# CurrentSensorV2_0.net
KiCad netlist of a schematic drawn in EAGLE
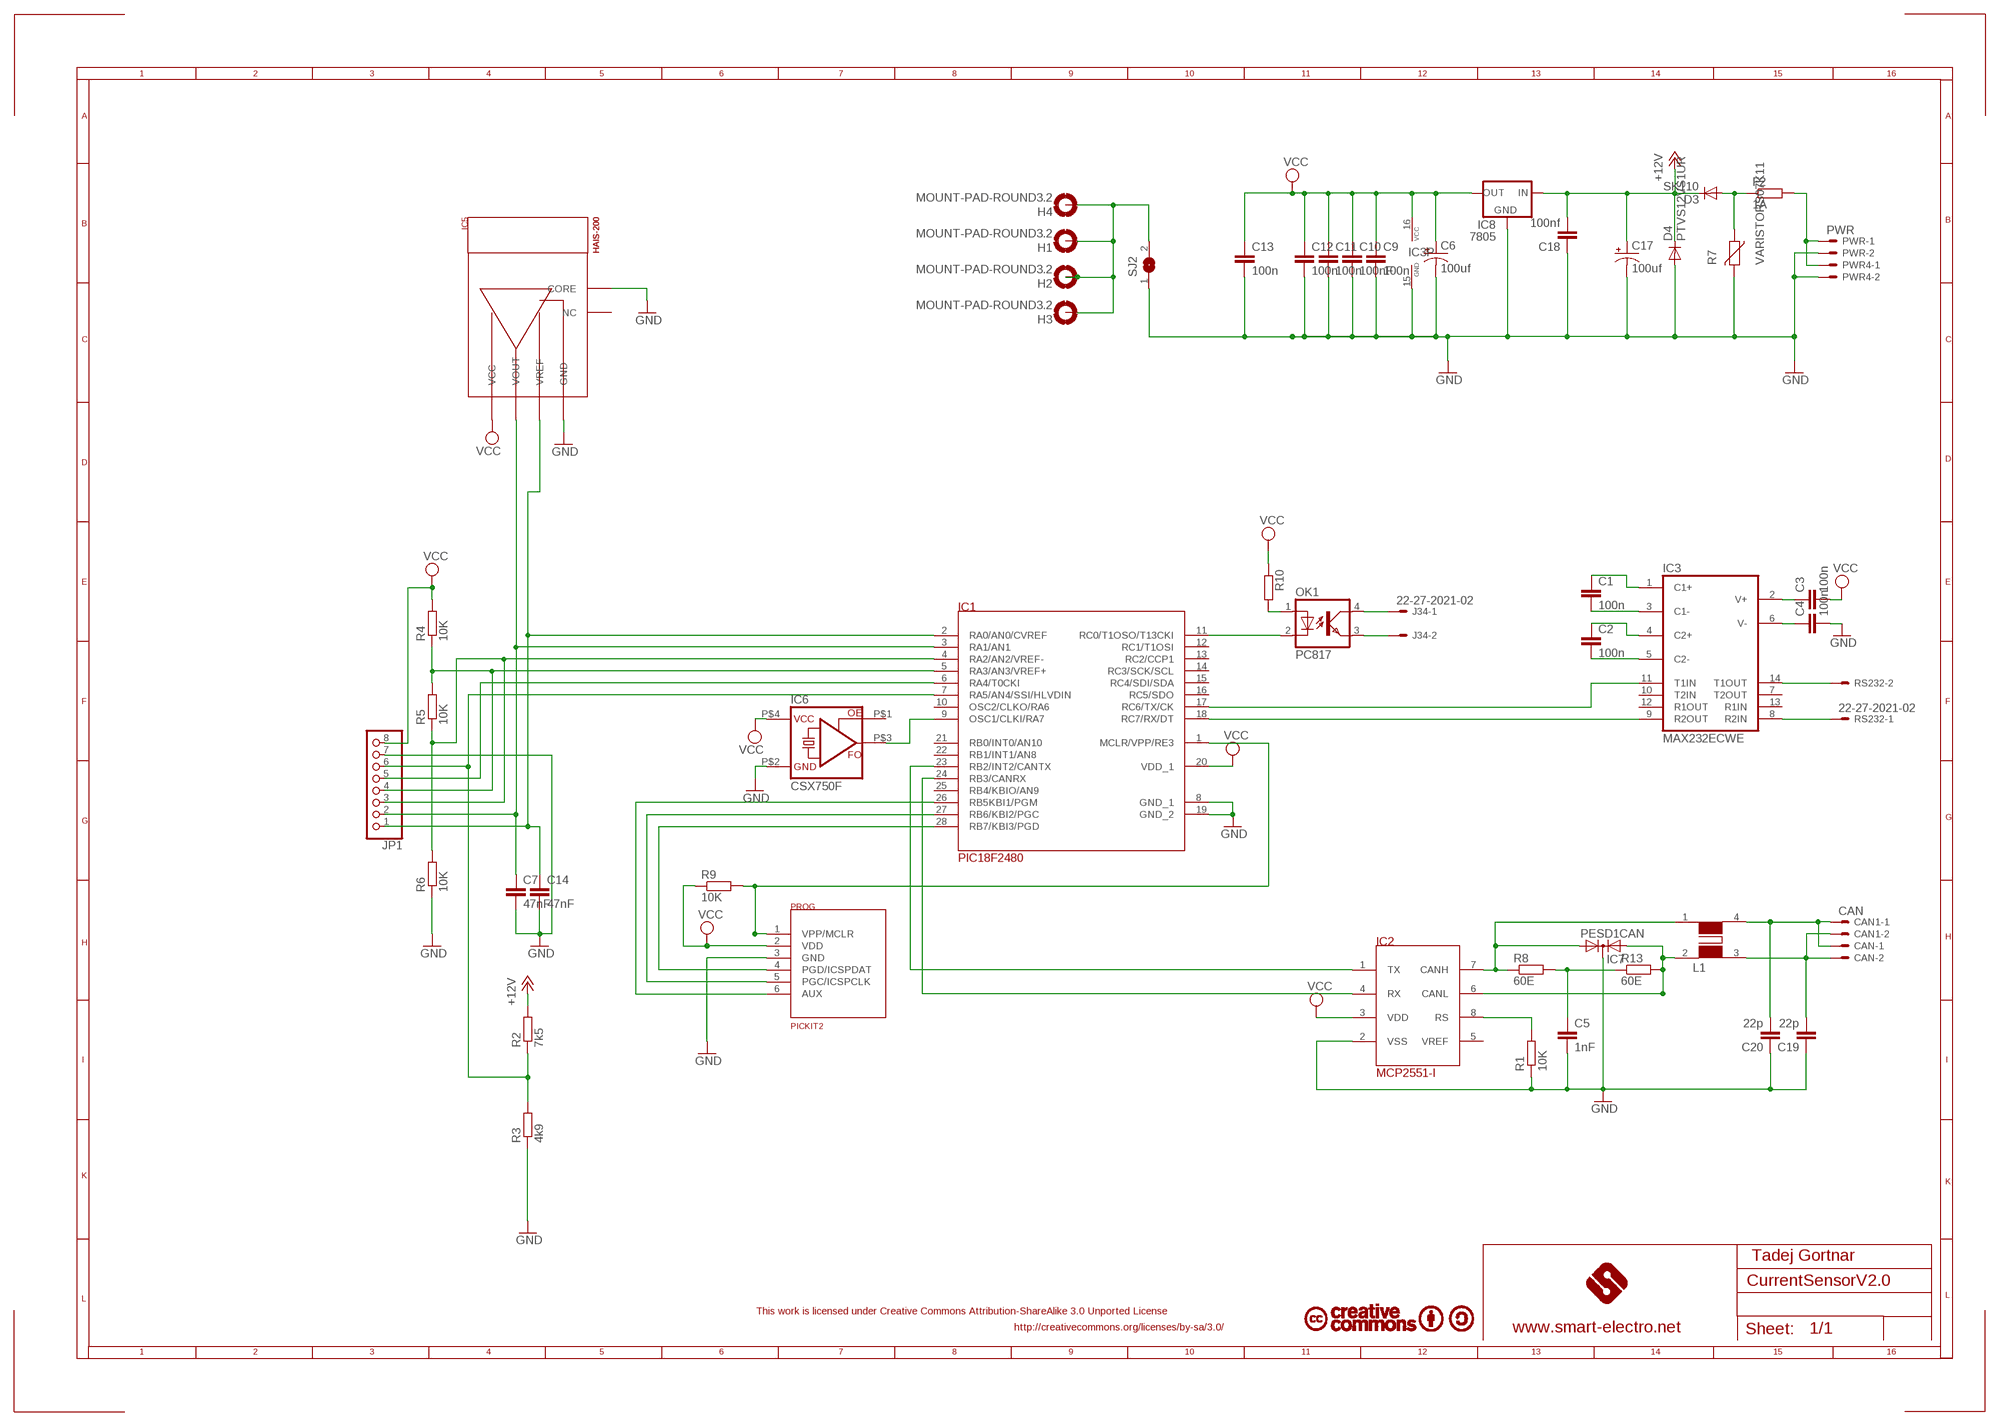
[diagram p0: schematic, sheet 1]

(export (version "E")
  (design (tool "Eeschema 10.0.6"))
  (components
    (comp (ref "C1")
      (value "100n")
      (footprint "eagle-import:C0805K")
      (libsource (lib "eagle-import") (part "C-EUC0805K"))
    )
    (comp (ref "C2")
      (value "100n")
      (footprint "eagle-import:C0805K")
      (libsource (lib "eagle-import") (part "C-EUC0805K"))
    )
    (comp (ref "C3")
      (value "100n")
      (footprint "eagle-import:C0805K")
      (libsource (lib "eagle-import") (part "C-EUC0805K"))
    )
    (comp (ref "C4")
      (value "100n")
      (footprint "eagle-import:C0805K")
      (libsource (lib "eagle-import") (part "C-EUC0805K"))
    )
    (comp (ref "C5")
      (value "1nF")
      (footprint "eagle-import:C0805")
      (libsource (lib "eagle-import") (part "C-EUC0805"))
    )
    (comp (ref "C6")
      (value "100uf")
      (footprint "eagle-import:PANASONIC_C")
      (libsource (lib "eagle-import") (part "CPOL-USC"))
    )
    (comp (ref "C7")
      (value "47nF")
      (footprint "eagle-import:C0805K")
      (libsource (lib "eagle-import") (part "C-EUC0805K"))
    )
    (comp (ref "C9")
      (value "100n")
      (footprint "eagle-import:C0805K")
      (libsource (lib "eagle-import") (part "C-EUC0805K"))
    )
    (comp (ref "C10")
      (value "100nF")
      (footprint "eagle-import:C0805K")
      (libsource (lib "eagle-import") (part "C-EUC0805K"))
    )
    (comp (ref "C11")
      (value "100n")
      (footprint "eagle-import:C0805K")
      (libsource (lib "eagle-import") (part "C-EUC0805K"))
    )
    (comp (ref "C12")
      (value "100n")
      (footprint "eagle-import:C0805K")
      (libsource (lib "eagle-import") (part "C-EUC0805K"))
    )
    (comp (ref "C13")
      (value "100n")
      (footprint "eagle-import:C0805K")
      (libsource (lib "eagle-import") (part "C-EUC0805K"))
    )
    (comp (ref "C14")
      (value "47nF")
      (footprint "eagle-import:C0805K")
      (libsource (lib "eagle-import") (part "C-EUC0805K"))
    )
    (comp (ref "C17")
      (value "100uf")
      (footprint "eagle-import:PANASONIC_C")
      (libsource (lib "eagle-import") (part "CPOL-USC"))
    )
    (comp (ref "C18")
      (value "100nf")
      (footprint "eagle-import:C0805")
      (libsource (lib "eagle-import") (part "resistor_C-EUC0805"))
    )
    (comp (ref "C19")
      (value "22p")
      (footprint "eagle-import:C0805")
      (libsource (lib "eagle-import") (part "C-EUC0805"))
    )
    (comp (ref "C20")
      (value "22p")
      (footprint "eagle-import:C0805")
      (libsource (lib "eagle-import") (part "C-EUC0805"))
    )
    (comp (ref "CAN")
      (value "CAN")
      (footprint "eagle-import:6410-02")
      (libsource (lib "eagle-import") (part "22-?-0227-2021"))
    )
    (comp (ref "CAN1")
      (value "CAN")
      (footprint "eagle-import:6410-02")
      (libsource (lib "eagle-import") (part "22-?-0227-2021"))
    )
    (comp (ref "D3")
      (value "SK110")
      (footprint "eagle-import:MINIMELF")
      (libsource (lib "eagle-import") (part "DIODE-MINIMELF"))
    )
    (comp (ref "D4")
      (value "PTVS12VS1UR")
      (footprint "eagle-import:SOD323-W")
      (libsource (lib "eagle-import") (part "DIODE-SOD323-W"))
    )
    (comp (ref "F2")
      (value "1A")
      (footprint "eagle-import:R1206")
      (libsource (lib "eagle-import") (part "resistor_R-EU_R1206"))
    )
    (comp (ref "H1")
      (value "MOUNT-PAD-ROUND3.2")
      (footprint "eagle-import:3,2-PAD")
      (libsource (lib "eagle-import") (part "MOUNT-PAD-ROUND3.2"))
    )
    (comp (ref "H2")
      (value "MOUNT-PAD-ROUND3.2")
      (footprint "eagle-import:3,2-PAD")
      (libsource (lib "eagle-import") (part "MOUNT-PAD-ROUND3.2"))
    )
    (comp (ref "H3")
      (value "MOUNT-PAD-ROUND3.2")
      (footprint "eagle-import:3,2-PAD")
      (libsource (lib "eagle-import") (part "MOUNT-PAD-ROUND3.2"))
    )
    (comp (ref "H4")
      (value "MOUNT-PAD-ROUND3.2")
      (footprint "eagle-import:3,2-PAD")
      (libsource (lib "eagle-import") (part "MOUNT-PAD-ROUND3.2"))
    )
    (comp (ref "IC1")
      (value "PIC18F2480")
      (footprint "eagle-import:SO-28W")
      (libsource (lib "eagle-import") (part "PIC18F280"))
    )
    (comp (ref "IC2")
      (value "MCP2551-I")
      (footprint "eagle-import:SO-08")
      (libsource (lib "eagle-import") (part "MCP2551"))
    )
    (comp (ref "IC3")
      (value "MAX232ECWE")
      (footprint "eagle-import:SO16L")
      (libsource (lib "eagle-import") (part "MAX232ECWE"))
    )
    (comp (ref "IC5")
      (value "HAIS-200")
      (footprint "eagle-import:HAIS-P")
      (libsource (lib "eagle-import") (part "HAIS-200"))
    )
    (comp (ref "IC6")
      (value "CSX750F")
      (footprint "eagle-import:CSX750")
      (libsource (lib "eagle-import") (part "CSX750F"))
    )
    (comp (ref "IC7")
      (value "PESD1CAN")
      (footprint "eagle-import:SOT23")
      (libsource (lib "eagle-import") (part "BAS70-06"))
    )
    (comp (ref "IC8")
      (value "7805")
      (footprint "eagle-import:SOT223")
      (libsource (lib "eagle-import") (part "78XXS'SOT223'"))
    )
    (comp (ref "J34")
      (value "22-27-2021-02")
      (footprint "eagle-import:6410-02")
      (libsource (lib "eagle-import") (part "22-?-0227-2021"))
    )
    (comp (ref "JP1")
      (value "PINHD-1X8")
      (footprint "eagle-import:1X08")
      (libsource (lib "eagle-import") (part "PINHD-1X8"))
    )
    (comp (ref "L1")
      (value "WE-DD_M/S")
      (footprint "eagle-import:WE-DD_M_S")
      (libsource (lib "eagle-import") (part "WE-DD_M/S"))
    )
    (comp (ref "OK1")
      (value "PC817")
      (footprint "eagle-import:DIL04")
      (libsource (lib "eagle-import") (part "PC817"))
    )
    (comp (ref "PROG")
      (value "PICKIT2")
      (footprint "eagle-import:PINHD-1X6")
      (libsource (lib "eagle-import") (part "PICKIT2"))
    )
    (comp (ref "PWR")
      (value "PWR")
      (footprint "eagle-import:6410-02")
      (libsource (lib "eagle-import") (part "22-?-0227-2021"))
    )
    (comp (ref "PWR4")
      (value "PWR")
      (footprint "eagle-import:6410-02")
      (libsource (lib "eagle-import") (part "22-?-0227-2021"))
    )
    (comp (ref "R1")
      (value "10K")
      (footprint "eagle-import:M0805")
      (libsource (lib "eagle-import") (part "R-EU_M0805"))
    )
    (comp (ref "R2")
      (value "7k5")
      (footprint "eagle-import:M0805")
      (libsource (lib "eagle-import") (part "R-EU_M0805"))
    )
    (comp (ref "R3")
      (value "4k9")
      (footprint "eagle-import:M0805")
      (libsource (lib "eagle-import") (part "R-EU_M0805"))
    )
    (comp (ref "R4")
      (value "10K")
      (footprint "eagle-import:M0805")
      (libsource (lib "eagle-import") (part "R-EU_M0805"))
    )
    (comp (ref "R5")
      (value "10K")
      (footprint "eagle-import:M0805")
      (libsource (lib "eagle-import") (part "R-EU_M0805"))
    )
    (comp (ref "R6")
      (value "10K")
      (footprint "eagle-import:M0805")
      (libsource (lib "eagle-import") (part "R-EU_M0805"))
    )
    (comp (ref "R7")
      (value "VARISTORS07K11")
      (footprint "eagle-import:S07K11")
      (libsource (lib "eagle-import") (part "VARISTORS07K11"))
    )
    (comp (ref "R8")
      (value "60E")
      (footprint "eagle-import:R0805")
      (libsource (lib "eagle-import") (part "R-EU_R0805"))
    )
    (comp (ref "R9")
      (value "10K")
      (footprint "eagle-import:M0805")
      (libsource (lib "eagle-import") (part "R-EU_M0805"))
    )
    (comp (ref "R10")
      (value "R-EU_M0805")
      (footprint "eagle-import:M0805")
      (libsource (lib "eagle-import") (part "R-EU_M0805"))
    )
    (comp (ref "R13")
      (value "60E")
      (footprint "eagle-import:R0805")
      (libsource (lib "eagle-import") (part "R-EU_R0805"))
    )
    (comp (ref "RS232")
      (value "22-27-2021-02")
      (footprint "eagle-import:6410-02")
      (libsource (lib "eagle-import") (part "22-?-0227-2021"))
    )
    (comp (ref "SJ2") (value "SJ") (footprint "eagle-import:SJ") (libsource (lib "eagle-import") (part "SJ")))
  )
  (nets
    (net (code "1") (name "+12V") (class "Default")
      (node (ref "C17") (pin "+") (pinfunction "+_+") (pintype "passive"))
      (node (ref "C18") (pin "2") (pinfunction "2_2") (pintype "passive"))
      (node (ref "D3") (pin "C") (pinfunction "C_C") (pintype "passive"))
      (node (ref "D4") (pin "C") (pinfunction "C_C") (pintype "passive"))
      (node (ref "IC8") (pin "1") (pinfunction "IN_1") (pintype "input"))
      (node (ref "R2") (pin "2") (pinfunction "2_2") (pintype "passive"))
    )
    (net (code "2") (name "GND") (class "Default")
      (node (ref "C10") (pin "2") (pinfunction "2_2") (pintype "passive"))
      (node (ref "C11") (pin "2") (pinfunction "2_2") (pintype "passive"))
      (node (ref "C12") (pin "2") (pinfunction "2_2") (pintype "passive"))
      (node (ref "C13") (pin "2") (pinfunction "2_2") (pintype "passive"))
      (node (ref "C14") (pin "2") (pinfunction "2_2") (pintype "passive"))
      (node (ref "C17") (pin "-") (pinfunction "-_-") (pintype "passive"))
      (node (ref "C18") (pin "1") (pinfunction "1_1") (pintype "passive"))
      (node (ref "C19") (pin "1") (pinfunction "1_1") (pintype "passive"))
      (node (ref "C20") (pin "1") (pinfunction "1_1") (pintype "passive"))
      (node (ref "C4") (pin "2") (pinfunction "2_2") (pintype "passive"))
      (node (ref "C5") (pin "2") (pinfunction "2_2") (pintype "passive"))
      (node (ref "C6") (pin "-") (pinfunction "-_-") (pintype "passive"))
      (node (ref "C7") (pin "2") (pinfunction "2_2") (pintype "passive"))
      (node (ref "C9") (pin "2") (pinfunction "2_2") (pintype "passive"))
      (node (ref "D4") (pin "A") (pinfunction "A_A") (pintype "passive"))
      (node (ref "IC1") (pin "19") (pinfunction "GND_2_19") (pintype "power_in"))
      (node (ref "IC1") (pin "8") (pinfunction "GND_1_8") (pintype "power_in"))
      (node (ref "IC2") (pin "2") (pinfunction "VSS_2") (pintype "power_in"))
      (node (ref "IC3") (pin "15") (pinfunction "GND_15") (pintype "power_in"))
      (node (ref "IC5") (pin "P$2") (pinfunction "GND_P$2") (pintype "power_in"))
      (node (ref "IC5") (pin "P$5") (pinfunction "CORE_P$5") (pintype "passive"))
      (node (ref "IC6") (pin "P$2") (pinfunction "GND_P$2") (pintype "power_in"))
      (node (ref "IC7") (pin "3") (pinfunction "C_3") (pintype "passive"))
      (node (ref "IC8") (pin "2") (pinfunction "GND_2") (pintype "input"))
      (node (ref "JP1") (pin "7") (pinfunction "7_7") (pintype "passive"))
      (node (ref "PROG") (pin "3") (pinfunction "GND_3") (pintype "bidirectional"))
      (node (ref "PWR") (pin "2") (pinfunction "S_2") (pintype "passive"))
      (node (ref "PWR4") (pin "2") (pinfunction "S_2") (pintype "passive"))
      (node (ref "R1") (pin "1") (pinfunction "1_1") (pintype "passive"))
      (node (ref "R3") (pin "1") (pinfunction "1_1") (pintype "passive"))
      (node (ref "R6") (pin "1") (pinfunction "1_1") (pintype "passive"))
      (node (ref "R7") (pin "2") (pinfunction "2_2") (pintype "passive"))
      (node (ref "SJ2") (pin "1") (pinfunction "1_1") (pintype "passive"))
    )
    (net (code "3") (name "Net-(C5-Pad1)") (class "Default")
      (node (ref "C5") (pin "1") (pinfunction "1_1") (pintype "passive"))
      (node (ref "R13") (pin "1") (pinfunction "1_1") (pintype "passive"))
      (node (ref "R8") (pin "2") (pinfunction "2_2") (pintype "passive"))
    )
    (net (code "4") (name "Net-(CAN1A-S)") (class "Default")
      (node (ref "C20") (pin "2") (pinfunction "2_2") (pintype "passive"))
      (node (ref "CAN") (pin "1") (pinfunction "S_1") (pintype "passive"))
      (node (ref "CAN1") (pin "1") (pinfunction "S_1") (pintype "passive"))
      (node (ref "L1") (pin "4") (pinfunction "3_4") (pintype "passive"))
    )
    (net (code "5") (name "Net-(CAN1B-S)") (class "Default")
      (node (ref "C19") (pin "2") (pinfunction "2_2") (pintype "passive"))
      (node (ref "CAN") (pin "2") (pinfunction "S_2") (pintype "passive"))
      (node (ref "CAN1") (pin "2") (pinfunction "S_2") (pintype "passive"))
      (node (ref "L1") (pin "3") (pinfunction "4_3") (pintype "passive"))
    )
    (net (code "6") (name "Net-(D3-PadA)") (class "Default")
      (node (ref "D3") (pin "A") (pinfunction "A_A") (pintype "passive"))
      (node (ref "F2") (pin "1") (pinfunction "1_1") (pintype "passive"))
      (node (ref "R7") (pin "1") (pinfunction "1_1") (pintype "passive"))
    )
    (net (code "7") (name "Net-(H1-MOUNT)") (class "Default")
      (node (ref "H1") (pin "B3,2") (pinfunction "MOUNT_B3,2") (pintype "passive"))
      (node (ref "H2") (pin "B3,2") (pinfunction "MOUNT_B3,2") (pintype "passive"))
      (node (ref "H3") (pin "B3,2") (pinfunction "MOUNT_B3,2") (pintype "passive"))
      (node (ref "H4") (pin "B3,2") (pinfunction "MOUNT_B3,2") (pintype "passive"))
      (node (ref "SJ2") (pin "2") (pinfunction "2_2") (pintype "passive"))
    )
    (net (code "8") (name "Net-(IC1-MCLR{slash}VPP{slash}RE3)") (class "Default")
      (node (ref "IC1") (pin "1") (pinfunction "MCLR/VPP/RE3_1") (pintype "input"))
      (node (ref "PROG") (pin "1") (pinfunction "VPP/MCLR_1") (pintype "bidirectional"))
      (node (ref "R9") (pin "2") (pinfunction "2_2") (pintype "passive"))
    )
    (net (code "9") (name "Net-(IC1-OSC1{slash}CLKI{slash}RA7)") (class "Default")
      (node (ref "IC1") (pin "9") (pinfunction "OSC1/CLKI/RA7_9") (pintype "bidirectional"))
      (node (ref "IC6") (pin "P$3") (pinfunction "FO_P$3") (pintype "output"))
    )
    (net (code "10") (name "Net-(IC1-RA0{slash}AN0{slash}CVREF)") (class "Default")
      (node (ref "C14") (pin "1") (pinfunction "1_1") (pintype "passive"))
      (node (ref "IC1") (pin "2") (pinfunction "RA0/AN0/CVREF_2") (pintype "bidirectional"))
      (node (ref "IC5") (pin "P$4") (pinfunction "VREF_P$4") (pintype "output"))
      (node (ref "JP1") (pin "1") (pinfunction "1_1") (pintype "passive"))
    )
    (net (code "11") (name "Net-(IC1-RA1{slash}AN1)") (class "Default")
      (node (ref "C7") (pin "1") (pinfunction "1_1") (pintype "passive"))
      (node (ref "IC1") (pin "3") (pinfunction "RA1/AN1_3") (pintype "bidirectional"))
      (node (ref "IC5") (pin "P$3") (pinfunction "VOUT_P$3") (pintype "output"))
      (node (ref "JP1") (pin "2") (pinfunction "2_2") (pintype "passive"))
    )
    (net (code "12") (name "Net-(IC1-RA2{slash}AN2{slash}VREF-)") (class "Default")
      (node (ref "IC1") (pin "4") (pinfunction "RA2/AN2/VREF-_4") (pintype "bidirectional"))
      (node (ref "JP1") (pin "3") (pinfunction "3_3") (pintype "passive"))
      (node (ref "R5") (pin "1") (pinfunction "1_1") (pintype "passive"))
      (node (ref "R6") (pin "2") (pinfunction "2_2") (pintype "passive"))
    )
    (net (code "13") (name "Net-(IC1-RA3{slash}AN3{slash}VREF+)") (class "Default")
      (node (ref "IC1") (pin "5") (pinfunction "RA3/AN3/VREF+_5") (pintype "bidirectional"))
      (node (ref "JP1") (pin "4") (pinfunction "4_4") (pintype "passive"))
      (node (ref "R4") (pin "1") (pinfunction "1_1") (pintype "passive"))
      (node (ref "R5") (pin "2") (pinfunction "2_2") (pintype "passive"))
    )
    (net (code "14") (name "Net-(IC1-RA4{slash}T0CKI)") (class "Default")
      (node (ref "IC1") (pin "6") (pinfunction "RA4/T0CKI_6") (pintype "bidirectional"))
      (node (ref "JP1") (pin "5") (pinfunction "5_5") (pintype "passive"))
    )
    (net (code "15") (name "Net-(IC1-RA5{slash}AN4{slash}SSI{slash}HLVDIN)") (class "Default")
      (node (ref "IC1") (pin "7") (pinfunction "RA5/AN4/SSI/HLVDIN_7") (pintype "bidirectional"))
      (node (ref "JP1") (pin "6") (pinfunction "6_6") (pintype "passive"))
      (node (ref "R2") (pin "1") (pinfunction "1_1") (pintype "passive"))
      (node (ref "R3") (pin "2") (pinfunction "2_2") (pintype "passive"))
    )
    (net (code "16") (name "Net-(IC1-RB2{slash}INT2{slash}CANTX)") (class "Default")
      (node (ref "IC1") (pin "23") (pinfunction "RB2/INT2/CANTX_23") (pintype "bidirectional"))
      (node (ref "IC2") (pin "1") (pinfunction "TX_1") (pintype "input"))
    )
    (net (code "17") (name "Net-(IC1-RB3{slash}CANRX)") (class "Default")
      (node (ref "IC1") (pin "24") (pinfunction "RB3/CANRX_24") (pintype "bidirectional"))
      (node (ref "IC2") (pin "4") (pinfunction "RX_4") (pintype "output"))
    )
    (net (code "18") (name "Net-(IC1-RB5KBI1{slash}PGM)") (class "Default")
      (node (ref "IC1") (pin "26") (pinfunction "RB5KBI1/PGM_26") (pintype "bidirectional"))
      (node (ref "PROG") (pin "6") (pinfunction "AUX_6") (pintype "bidirectional"))
    )
    (net (code "19") (name "Net-(IC1-RB6{slash}KBI2{slash}PGC)") (class "Default")
      (node (ref "IC1") (pin "27") (pinfunction "RB6/KBI2/PGC_27") (pintype "bidirectional"))
      (node (ref "PROG") (pin "5") (pinfunction "PGC/ICSPCLK_5") (pintype "bidirectional"))
    )
    (net (code "20") (name "Net-(IC1-RB7{slash}KBI3{slash}PGD)") (class "Default")
      (node (ref "IC1") (pin "28") (pinfunction "RB7/KBI3/PGD_28") (pintype "bidirectional"))
      (node (ref "PROG") (pin "4") (pinfunction "PGD/ICSPDAT_4") (pintype "bidirectional"))
    )
    (net (code "21") (name "Net-(IC1-RC0{slash}T1OSO{slash}T13CKI)") (class "Default")
      (node (ref "IC1") (pin "11") (pinfunction "RC0/T1OSO/T13CKI_11") (pintype "bidirectional"))
      (node (ref "OK1") (pin "2") (pinfunction "C_2") (pintype "passive"))
    )
    (net (code "22") (name "Net-(IC1-RC6{slash}TX{slash}CK)") (class "Default")
      (node (ref "IC1") (pin "17") (pinfunction "RC6/TX/CK_17") (pintype "bidirectional"))
      (node (ref "IC3") (pin "11") (pinfunction "T1IN_11") (pintype "input"))
    )
    (net (code "23") (name "Net-(IC1-RC7{slash}RX{slash}DT)") (class "Default")
      (node (ref "IC1") (pin "18") (pinfunction "RC7/RX/DT_18") (pintype "bidirectional"))
      (node (ref "IC3") (pin "9") (pinfunction "R2OUT_9") (pintype "output"))
    )
    (net (code "24") (name "Net-(IC2-CANH)") (class "Default")
      (node (ref "IC2") (pin "7") (pinfunction "CANH_7") (pintype "bidirectional"))
      (node (ref "IC7") (pin "1") (pinfunction "A1_1") (pintype "passive"))
      (node (ref "L1") (pin "1") (pinfunction "2_1") (pintype "passive"))
      (node (ref "R8") (pin "1") (pinfunction "1_1") (pintype "passive"))
    )
    (net (code "25") (name "Net-(IC2-CANL)") (class "Default")
      (node (ref "IC2") (pin "6") (pinfunction "CANL_6") (pintype "bidirectional"))
      (node (ref "IC7") (pin "2") (pinfunction "A2_2") (pintype "passive"))
      (node (ref "L1") (pin "2") (pinfunction "1_2") (pintype "passive"))
      (node (ref "R13") (pin "2") (pinfunction "2_2") (pintype "passive"))
    )
    (net (code "26") (name "Net-(IC2-RS)") (class "Default")
      (node (ref "IC2") (pin "8") (pinfunction "RS_8") (pintype "passive"))
      (node (ref "R1") (pin "2") (pinfunction "2_2") (pintype "passive"))
    )
    (net (code "27") (name "Net-(IC3A-C1+)") (class "Default")
      (node (ref "C1") (pin "1") (pinfunction "1_1") (pintype "passive"))
      (node (ref "IC3") (pin "1") (pinfunction "C1+_1") (pintype "bidirectional"))
    )
    (net (code "28") (name "Net-(IC3A-C1-)") (class "Default")
      (node (ref "C1") (pin "2") (pinfunction "2_2") (pintype "passive"))
      (node (ref "IC3") (pin "3") (pinfunction "C1-_3") (pintype "bidirectional"))
    )
    (net (code "29") (name "Net-(IC3A-C2+)") (class "Default")
      (node (ref "C2") (pin "1") (pinfunction "1_1") (pintype "passive"))
      (node (ref "IC3") (pin "4") (pinfunction "C2+_4") (pintype "bidirectional"))
    )
    (net (code "30") (name "Net-(IC3A-C2-)") (class "Default")
      (node (ref "C2") (pin "2") (pinfunction "2_2") (pintype "passive"))
      (node (ref "IC3") (pin "5") (pinfunction "C2-_5") (pintype "bidirectional"))
    )
    (net (code "31") (name "Net-(IC3A-R2IN)") (class "Default")
      (node (ref "IC3") (pin "8") (pinfunction "R2IN_8") (pintype "input"))
      (node (ref "RS232") (pin "1") (pinfunction "S_1") (pintype "passive"))
    )
    (net (code "32") (name "Net-(IC3A-T1OUT)") (class "Default")
      (node (ref "IC3") (pin "14") (pinfunction "T1OUT_14") (pintype "output"))
      (node (ref "RS232") (pin "2") (pinfunction "S_2") (pintype "passive"))
    )
    (net (code "33") (name "Net-(IC3A-V+)") (class "Default")
      (node (ref "C3") (pin "1") (pinfunction "1_1") (pintype "passive"))
      (node (ref "IC3") (pin "2") (pinfunction "V+_2") (pintype "bidirectional"))
    )
    (net (code "34") (name "Net-(IC3A-V-)") (class "Default")
      (node (ref "C4") (pin "1") (pinfunction "1_1") (pintype "passive"))
      (node (ref "IC3") (pin "6") (pinfunction "V-_6") (pintype "bidirectional"))
    )
    (net (code "35") (name "Net-(J34A-S)") (class "Default")
      (node (ref "J34") (pin "1") (pinfunction "S_1") (pintype "passive"))
      (node (ref "OK1") (pin "4") (pinfunction "COL_4") (pintype "passive"))
    )
    (net (code "36") (name "Net-(J34B-S)") (class "Default")
      (node (ref "J34") (pin "2") (pinfunction "S_2") (pintype "passive"))
      (node (ref "OK1") (pin "3") (pinfunction "EMIT_3") (pintype "passive"))
    )
    (net (code "37") (name "Net-(OK1-A)") (class "Default")
      (node (ref "OK1") (pin "1") (pinfunction "A_1") (pintype "passive"))
      (node (ref "R10") (pin "2") (pinfunction "2_2") (pintype "passive"))
    )
    (net (code "38") (name "Net-(PWR4A-S)") (class "Default")
      (node (ref "F2") (pin "2") (pinfunction "2_2") (pintype "passive"))
      (node (ref "PWR") (pin "1") (pinfunction "S_1") (pintype "passive"))
      (node (ref "PWR4") (pin "1") (pinfunction "S_1") (pintype "passive"))
    )
    (net (code "39") (name "VCC") (class "Default")
      (node (ref "C10") (pin "1") (pinfunction "1_1") (pintype "passive"))
      (node (ref "C11") (pin "1") (pinfunction "1_1") (pintype "passive"))
      (node (ref "C12") (pin "1") (pinfunction "1_1") (pintype "passive"))
      (node (ref "C13") (pin "1") (pinfunction "1_1") (pintype "passive"))
      (node (ref "C3") (pin "2") (pinfunction "2_2") (pintype "passive"))
      (node (ref "C6") (pin "+") (pinfunction "+_+") (pintype "passive"))
      (node (ref "C9") (pin "1") (pinfunction "1_1") (pintype "passive"))
      (node (ref "IC1") (pin "20") (pinfunction "VDD_1_20") (pintype "power_in"))
      (node (ref "IC2") (pin "3") (pinfunction "VDD_3") (pintype "power_in"))
      (node (ref "IC3") (pin "16") (pinfunction "VCC_16") (pintype "power_in"))
      (node (ref "IC5") (pin "P$1") (pinfunction "VCC_P$1") (pintype "power_in"))
      (node (ref "IC6") (pin "P$4") (pinfunction "VCC_P$4") (pintype "power_in"))
      (node (ref "IC8") (pin "3") (pinfunction "OUT_3") (pintype "passive"))
      (node (ref "JP1") (pin "8") (pinfunction "8_8") (pintype "passive"))
      (node (ref "PROG") (pin "2") (pinfunction "VDD_2") (pintype "bidirectional"))
      (node (ref "R10") (pin "1") (pinfunction "1_1") (pintype "passive"))
      (node (ref "R4") (pin "2") (pinfunction "2_2") (pintype "passive"))
      (node (ref "R9") (pin "1") (pinfunction "1_1") (pintype "passive"))
    )
    (net (code "40") (name "unconnected-(IC1-OSC2{slash}CLKO{slash}RA6-Pad10)") (class "Default")
      (node (ref "IC1") (pin "10") (pinfunction "OSC2/CLKO/RA6_10") (pintype "bidirectional"))
    )
    (net (code "41") (name "unconnected-(IC1-RB0{slash}INT0{slash}AN10-Pad21)") (class "Default")
      (node (ref "IC1") (pin "21") (pinfunction "RB0/INT0/AN10_21") (pintype "bidirectional"))
    )
    (net (code "42") (name "unconnected-(IC1-RB1{slash}INT1{slash}AN8-Pad22)") (class "Default")
      (node (ref "IC1") (pin "22") (pinfunction "RB1/INT1/AN8_22") (pintype "bidirectional"))
    )
    (net (code "43") (name "unconnected-(IC1-RB4{slash}KBIO{slash}AN9-Pad25)") (class "Default")
      (node (ref "IC1") (pin "25") (pinfunction "RB4/KBIO/AN9_25") (pintype "bidirectional"))
    )
    (net (code "44") (name "unconnected-(IC1-RC1{slash}T1OSI-Pad12)") (class "Default")
      (node (ref "IC1") (pin "12") (pinfunction "RC1/T1OSI_12") (pintype "bidirectional"))
    )
    (net (code "45") (name "unconnected-(IC1-RC2{slash}CCP1-Pad13)") (class "Default")
      (node (ref "IC1") (pin "13") (pinfunction "RC2/CCP1_13") (pintype "bidirectional"))
    )
    (net (code "46") (name "unconnected-(IC1-RC3{slash}SCK{slash}SCL-Pad14)") (class "Default")
      (node (ref "IC1") (pin "14") (pinfunction "RC3/SCK/SCL_14") (pintype "bidirectional"))
    )
    (net (code "47") (name "unconnected-(IC1-RC4{slash}SDI{slash}SDA-Pad15)") (class "Default")
      (node (ref "IC1") (pin "15") (pinfunction "RC4/SDI/SDA_15") (pintype "bidirectional"))
    )
    (net (code "48") (name "unconnected-(IC1-RC5{slash}SDO-Pad16)") (class "Default")
      (node (ref "IC1") (pin "16") (pinfunction "RC5/SDO_16") (pintype "bidirectional"))
    )
    (net (code "49") (name "unconnected-(IC2-VREF-Pad5)") (class "Default")
      (node (ref "IC2") (pin "5") (pinfunction "VREF_5") (pintype "output"))
    )
    (net (code "50") (name "unconnected-(IC3A-R1IN-Pad13)") (class "Default")
      (node (ref "IC3") (pin "13") (pinfunction "R1IN_13") (pintype "input"))
    )
    (net (code "51") (name "unconnected-(IC3A-R1OUT-Pad12)") (class "Default")
      (node (ref "IC3") (pin "12") (pinfunction "R1OUT_12") (pintype "output"))
    )
    (net (code "52") (name "unconnected-(IC3A-T2IN-Pad10)") (class "Default")
      (node (ref "IC3") (pin "10") (pinfunction "T2IN_10") (pintype "input"))
    )
    (net (code "53") (name "unconnected-(IC3A-T2OUT-Pad7)") (class "Default")
      (node (ref "IC3") (pin "7") (pinfunction "T2OUT_7") (pintype "output"))
    )
    (net (code "54") (name "unconnected-(IC5-NC-PadP$6)") (class "Default")
      (node (ref "IC5") (pin "P$6") (pinfunction "NC_P$6") (pintype "passive"))
    )
    (net (code "55") (name "unconnected-(IC6-OE-PadP$1)") (class "Default")
      (node (ref "IC6") (pin "P$1") (pinfunction "OE_P$1") (pintype "input"))
    )
  )
)
